# SCH_X2FA_2025-07-30.net
KiCad netlist of a schematic drawn in EasyEDA
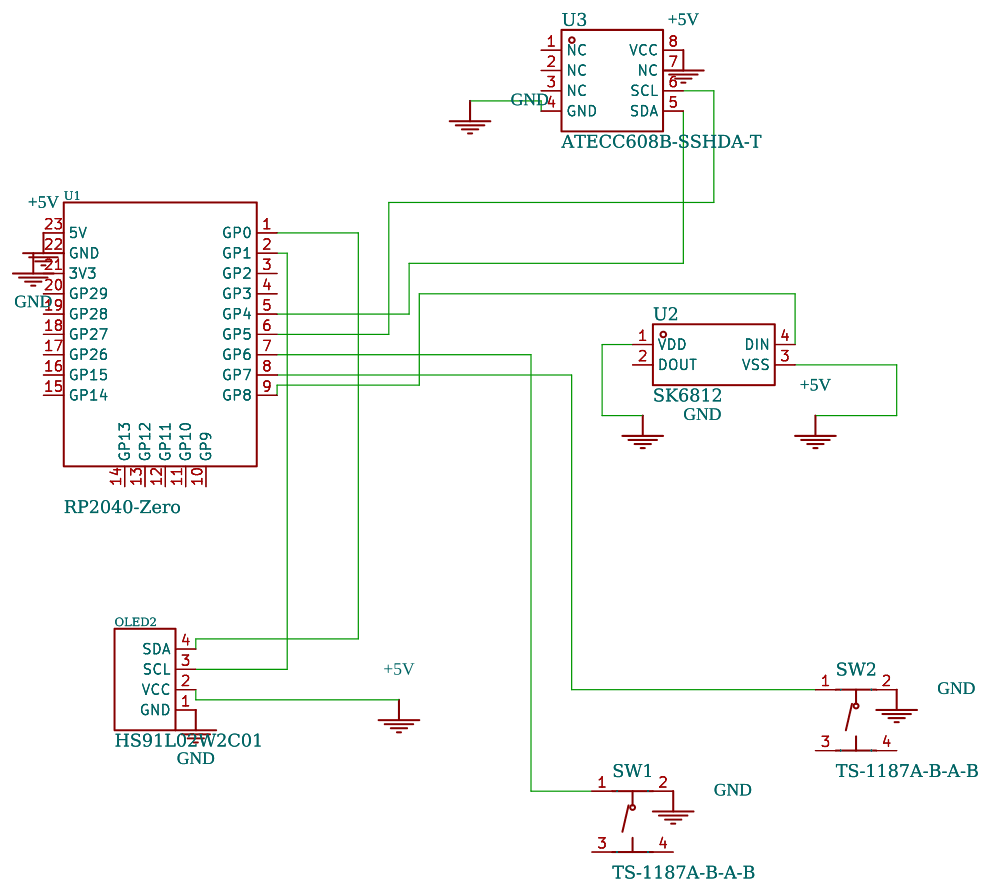
[diagram p0: schematic sheet]

(export (version "E")
  (design (tool "Eeschema 10.0.6"))
  (components
    (comp (ref "OLED2")
      (value "HS91L02W2C01")
      (fields (field (name "Manufacturer") "HS(汉昇)"))
      (libsource (lib "") (part "Unknown_95_-115"))
    )
    (comp (ref "SW1")
      (value "TS-1187A-B-A-B")
      (fields (field (name "Manufacturer") "XKB Connectivity(中国星坤)"))
      (libsource (lib "") (part "Unknown_330_-50"))
    )
    (comp (ref "SW2")
      (value "TS-1187A-B-A-B")
      (fields (field (name "Manufacturer") "XKB Connectivity(中国星坤)"))
      (libsource (lib "") (part "Unknown_440_-100"))
    )
    (comp (ref "U1")
      (value "RP2040-Zero")
      (fields (field (name "Manufacturer") "Waveshare(微雪电子)"))
      (libsource (lib "") (part "Unknown_100_-280"))
    )
    (comp (ref "U2") (value "SK6812") (libsource (lib "") (part "Unknown_370_-275")))
    (comp (ref "U3")
      (value "ATECC608B-SSHDA-T")
      (fields (field (name "Manufacturer") "MICROCHIP(美国微芯)"))
      (libsource (lib "") (part "Unknown_320_-410"))
    )
  )
  (nets
    (net (code "1") (name "+5V") (class "Default")
      (node (ref "OLED2") (pin "2") (pinfunction "VCC_2") (pintype "unspecified"))
      (node (ref "U1") (pin "23") (pinfunction "5V_23") (pintype "unspecified"))
      (node (ref "U2") (pin "3") (pinfunction "VSS_3") (pintype "unspecified"))
      (node (ref "U3") (pin "8") (pinfunction "VCC_8") (pintype "unspecified"))
    )
    (net (code "2") (name "GND") (class "Default")
      (node (ref "OLED2") (pin "1") (pinfunction "GND_1") (pintype "unspecified"))
      (node (ref "SW1") (pin "2") (pinfunction "B_2") (pintype "unspecified"))
      (node (ref "SW2") (pin "2") (pinfunction "B_2") (pintype "unspecified"))
      (node (ref "U2") (pin "1") (pinfunction "VDD_1") (pintype "unspecified"))
      (node (ref "U3") (pin "4") (pinfunction "GND_4") (pintype "unspecified"))
    )
    (net (code "3") (name "Net-(OLED2-SCL)") (class "Default")
      (node (ref "OLED2") (pin "3") (pinfunction "SCL_3") (pintype "unspecified"))
      (node (ref "U1") (pin "2") (pinfunction "GP1_2") (pintype "unspecified"))
    )
    (net (code "4") (name "Net-(OLED2-SDA)") (class "Default")
      (node (ref "OLED2") (pin "4") (pinfunction "SDA_4") (pintype "unspecified"))
      (node (ref "U1") (pin "1") (pinfunction "GP0_1") (pintype "unspecified"))
    )
    (net (code "5") (name "Net-(SW1-A)") (class "Default")
      (node (ref "SW1") (pin "1") (pinfunction "A_1") (pintype "unspecified"))
      (node (ref "U1") (pin "7") (pinfunction "GP6_7") (pintype "unspecified"))
    )
    (net (code "6") (name "Net-(SW2-A)") (class "Default")
      (node (ref "SW2") (pin "1") (pinfunction "A_1") (pintype "unspecified"))
      (node (ref "U1") (pin "8") (pinfunction "GP7_8") (pintype "unspecified"))
    )
    (net (code "7") (name "Net-(U1-GP4)") (class "Default")
      (node (ref "U1") (pin "5") (pinfunction "GP4_5") (pintype "unspecified"))
      (node (ref "U3") (pin "5") (pinfunction "SDA_5") (pintype "unspecified"))
    )
    (net (code "8") (name "Net-(U1-GP5)") (class "Default")
      (node (ref "U1") (pin "6") (pinfunction "GP5_6") (pintype "unspecified"))
      (node (ref "U3") (pin "6") (pinfunction "SCL_6") (pintype "unspecified"))
    )
    (net (code "9") (name "Net-(U1-GP8)") (class "Default")
      (node (ref "U1") (pin "9") (pinfunction "GP8_9") (pintype "unspecified"))
      (node (ref "U2") (pin "4") (pinfunction "DIN_4") (pintype "unspecified"))
    )
    (net (code "10") (name "unconnected-(SW1-C-Pad3)") (class "Default")
      (node (ref "SW1") (pin "3") (pinfunction "C_3") (pintype "unspecified"))
    )
    (net (code "11") (name "unconnected-(SW1-D-Pad4)") (class "Default")
      (node (ref "SW1") (pin "4") (pinfunction "D_4") (pintype "unspecified"))
    )
    (net (code "12") (name "unconnected-(SW2-C-Pad3)") (class "Default")
      (node (ref "SW2") (pin "3") (pinfunction "C_3") (pintype "unspecified"))
    )
    (net (code "13") (name "unconnected-(SW2-D-Pad4)") (class "Default")
      (node (ref "SW2") (pin "4") (pinfunction "D_4") (pintype "unspecified"))
    )
    (net (code "14") (name "unconnected-(U1-3V3-Pad21)") (class "Default")
      (node (ref "U1") (pin "21") (pinfunction "3V3_21") (pintype "unspecified"))
    )
    (net (code "15") (name "unconnected-(U1-GND-Pad22)") (class "Default")
      (node (ref "U1") (pin "22") (pinfunction "GND_22") (pintype "unspecified"))
    )
    (net (code "16") (name "unconnected-(U1-GP2-Pad3)") (class "Default")
      (node (ref "U1") (pin "3") (pinfunction "GP2_3") (pintype "unspecified"))
    )
    (net (code "17") (name "unconnected-(U1-GP3-Pad4)") (class "Default")
      (node (ref "U1") (pin "4") (pinfunction "GP3_4") (pintype "unspecified"))
    )
    (net (code "18") (name "unconnected-(U1-GP9-Pad10)") (class "Default")
      (node (ref "U1") (pin "10") (pinfunction "GP9_10") (pintype "unspecified"))
    )
    (net (code "19") (name "unconnected-(U1-GP10-Pad11)") (class "Default")
      (node (ref "U1") (pin "11") (pinfunction "GP10_11") (pintype "unspecified"))
    )
    (net (code "20") (name "unconnected-(U1-GP11-Pad12)") (class "Default")
      (node (ref "U1") (pin "12") (pinfunction "GP11_12") (pintype "unspecified"))
    )
    (net (code "21") (name "unconnected-(U1-GP12-Pad13)") (class "Default")
      (node (ref "U1") (pin "13") (pinfunction "GP12_13") (pintype "unspecified"))
    )
    (net (code "22") (name "unconnected-(U1-GP13-Pad14)") (class "Default")
      (node (ref "U1") (pin "14") (pinfunction "GP13_14") (pintype "unspecified"))
    )
    (net (code "23") (name "unconnected-(U1-GP14-Pad15)") (class "Default")
      (node (ref "U1") (pin "15") (pinfunction "GP14_15") (pintype "unspecified"))
    )
    (net (code "24") (name "unconnected-(U1-GP15-Pad16)") (class "Default")
      (node (ref "U1") (pin "16") (pinfunction "GP15_16") (pintype "unspecified"))
    )
    (net (code "25") (name "unconnected-(U1-GP26-Pad17)") (class "Default")
      (node (ref "U1") (pin "17") (pinfunction "GP26_17") (pintype "unspecified"))
    )
    (net (code "26") (name "unconnected-(U1-GP27-Pad18)") (class "Default")
      (node (ref "U1") (pin "18") (pinfunction "GP27_18") (pintype "unspecified"))
    )
    (net (code "27") (name "unconnected-(U1-GP28-Pad19)") (class "Default")
      (node (ref "U1") (pin "19") (pinfunction "GP28_19") (pintype "unspecified"))
    )
    (net (code "28") (name "unconnected-(U1-GP29-Pad20)") (class "Default")
      (node (ref "U1") (pin "20") (pinfunction "GP29_20") (pintype "unspecified"))
    )
    (net (code "29") (name "unconnected-(U2-DOUT-Pad2)") (class "Default")
      (node (ref "U2") (pin "2") (pinfunction "DOUT_2") (pintype "unspecified"))
    )
    (net (code "30") (name "unconnected-(U3-NC-Pad1)") (class "Default")
      (node (ref "U3") (pin "1") (pinfunction "NC_1") (pintype "unspecified"))
    )
    (net (code "31") (name "unconnected-(U3-NC-Pad2)") (class "Default")
      (node (ref "U3") (pin "2") (pinfunction "NC_2") (pintype "unspecified"))
    )
    (net (code "32") (name "unconnected-(U3-NC-Pad3)") (class "Default")
      (node (ref "U3") (pin "3") (pinfunction "NC_3") (pintype "unspecified"))
    )
    (net (code "33") (name "unconnected-(U3-NC-Pad7)") (class "Default")
      (node (ref "U3") (pin "7") (pinfunction "NC_7") (pintype "unspecified"))
    )
  )
)
